# power.net
KiCad netlist of a schematic drawn in Altium Designer
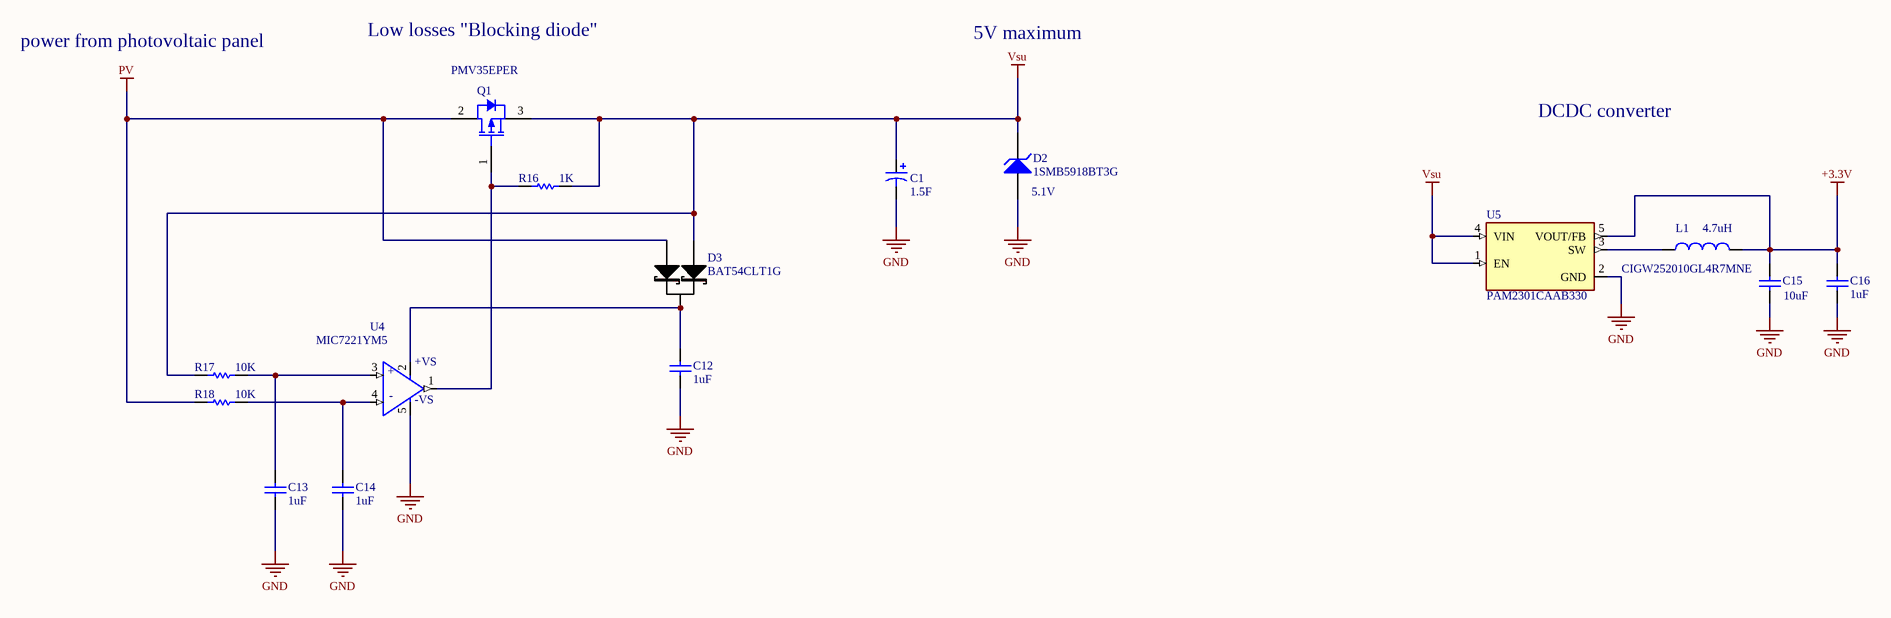
[diagram p0: power.SchDoc]

(export (version "E")
  (design (tool "Eeschema 10.0.6"))
  (components
    (comp (ref "C1")
      (value "1.5F")
      (footprint "SCMR22H155PSBB0")
      (description "Polarized Capacitor (Radial)")
      (fields (field (name "Comment") "Cap Pol1") (field (name "PUBLISHER") "Altium Limited"))
      (libsource (lib "Miscellaneous Devices") (part "Cap Pol1"))
    )
    (comp (ref "C12")
      (value "1uF")
      (footprint "6-0805_M")
      (description "Capacitor")
      (fields (field (name "PUBLISHER") "Altium Limited"))
      (libsource (lib "Miscellaneous Devices") (part "Cap"))
    )
    (comp (ref "C13")
      (value "1uF")
      (footprint "6-0805_M")
      (description "Capacitor")
      (fields (field (name "PUBLISHER") "Altium Limited"))
      (libsource (lib "Miscellaneous Devices") (part "Cap"))
    )
    (comp (ref "C14")
      (value "1uF")
      (footprint "6-0805_M")
      (description "Capacitor")
      (fields (field (name "PUBLISHER") "Altium Limited"))
      (libsource (lib "Miscellaneous Devices") (part "Cap"))
    )
    (comp (ref "C15")
      (value "10uF")
      (footprint "6-0805_M")
      (fields (field (name "PUBLISHER") "Altium Limited"))
      (libsource (lib "Miscellaneous Devices") (part "Cap"))
    )
    (comp (ref "C16")
      (value "1uF")
      (footprint "6-0805_M")
      (description "Capacitor")
      (fields (field (name "PUBLISHER") "Altium Limited"))
      (libsource (lib "Miscellaneous Devices") (part "Cap"))
    )
    (comp (ref "D2")
      (value "1SMB5918BT3G")
      (footprint "SMB")
      (description "Zener Diode")
      (fields (field (name "ALTIUM_VALUE") "5.1V") (field (name "PUBLISHER") "Altium Limited"))
      (libsource (lib "Miscellaneous Devices") (part "D Zener"))
    )
    (comp (ref "D3")
      (value "BAT54CLT1G")
      (footprint "SOT23-DUODIODE")
      (description "DUAL SCHOTTKY DIODE COMMON CATHODE")
      (fields
        (field (name "MANUFACTURER") "NXP Semiconductors")
        (field (name "MANUFACTURER PART NUMBER") "BAT54C,215")
      )
      (libsource (lib "vh_altium_library") (part "BAT54C-SOT23"))
    )
    (comp (ref "L1")
      (value "CIGW252010GL4R7MNE")
      (footprint "INDUCTOR_2520 - duplicate1")
      (description "Inductor")
      (fields (field (name "ALTIUM_VALUE") "4.7uH") (field (name "PUBLISHER") "Altium Limited"))
      (libsource (lib "Miscellaneous Devices") (part "Inductor"))
    )
    (comp (ref "Q1")
      (value "PMV35EPER")
      (footprint "PMV35EPER")
      (description "P-Channel MOSFET")
      (fields (field (name "PUBLISHER") "Altium Limited"))
      (libsource (lib "laf") (part "MOSFET-P"))
    )
    (comp (ref "R16")
      (value "1K")
      (footprint "6-0805_N")
      (description "Resistor")
      (fields (field (name "PUBLISHER") "Altium Limited"))
      (libsource (lib "Miscellaneous Devices") (part "Res1"))
    )
    (comp (ref "R17")
      (value "10K")
      (footprint "6-0805_N")
      (description "Resistor")
      (fields (field (name "PUBLISHER") "Altium Limited"))
      (libsource (lib "Miscellaneous Devices") (part "Res1"))
    )
    (comp (ref "R18")
      (value "10K")
      (footprint "6-0805_N")
      (description "Resistor")
      (fields (field (name "PUBLISHER") "Altium Limited"))
      (libsource (lib "Miscellaneous Devices") (part "Res1"))
    )
    (comp (ref "U4")
      (value "MIC7221YM5")
      (footprint "MIC7221YM5")
      (description "Comparator General Purpose Open Drain SOT-23-5")
      (fields (field (name "MP") "MIC7221YM5-TR") (field (name "MF") "Microchip"))
      (libsource (lib "laf") (part "MIC7221YM5-TR"))
    )
    (comp (ref "U5")
      (value "PAM2301CAAB330")
      (footprint "SOT95P280X100-5N")
      (description "Buck Switching Regulator IC Positive Fixed 1.2V 1 Output 800mA SOT-23-5 Thin, TSOT-23-5")
      (fields (field (name "MF") "Diodes Inc.") (field (name "MP") "PAM2301CAAB120"))
      (libsource (lib "laf") (part "PAM2301CAAB120"))
    )
  )
  (nets
    (net (code "1") (name "+3.3V") (class "Default")
      (node (ref "C15") (pin "2") (pinfunction "2_2") (pintype "passive"))
      (node (ref "C16") (pin "2") (pinfunction "2_2") (pintype "passive"))
      (node (ref "L1") (pin "2") (pinfunction "2_2") (pintype "passive"))
      (node (ref "U5") (pin "5") (pinfunction "VOUT/FB_5") (pintype "output"))
    )
    (net (code "2") (name "GND") (class "Default")
      (node (ref "C1") (pin "2") (pinfunction "2_2") (pintype "passive"))
      (node (ref "C12") (pin "1") (pinfunction "1_1") (pintype "passive"))
      (node (ref "C13") (pin "1") (pinfunction "1_1") (pintype "passive"))
      (node (ref "C14") (pin "1") (pinfunction "1_1") (pintype "passive"))
      (node (ref "C15") (pin "1") (pinfunction "1_1") (pintype "passive"))
      (node (ref "C16") (pin "1") (pinfunction "1_1") (pintype "passive"))
      (node (ref "D2") (pin "1") (pinfunction "A_1") (pintype "passive"))
      (node (ref "U4") (pin "5") (pinfunction "-VS_5") (pintype "power_in"))
      (node (ref "U5") (pin "2") (pinfunction "GND_2") (pintype "power_in"))
    )
    (net (code "3") (name "Net-(Q1-G)") (class "Default")
      (node (ref "Q1") (pin "1") (pinfunction "G_1") (pintype "passive"))
      (node (ref "R16") (pin "1") (pinfunction "1_1") (pintype "passive"))
      (node (ref "U4") (pin "1") (pinfunction "OUT_1") (pintype "output"))
    )
    (net (code "4") (name "Net-(U4-+VS)") (class "Default")
      (node (ref "C12") (pin "2") (pinfunction "2_2") (pintype "passive"))
      (node (ref "D3") (pin "3") (pinfunction "3_3") (pintype "passive"))
      (node (ref "U4") (pin "2") (pinfunction "+VS_2") (pintype "power_in"))
    )
    (net (code "5") (name "Net-(U4-IN+)") (class "Default")
      (node (ref "C13") (pin "2") (pinfunction "2_2") (pintype "passive"))
      (node (ref "R17") (pin "2") (pinfunction "2_2") (pintype "passive"))
      (node (ref "U4") (pin "3") (pinfunction "IN+_3") (pintype "input"))
    )
    (net (code "6") (name "Net-(U4-IN-)") (class "Default")
      (node (ref "C14") (pin "2") (pinfunction "2_2") (pintype "passive"))
      (node (ref "R18") (pin "2") (pinfunction "2_2") (pintype "passive"))
      (node (ref "U4") (pin "4") (pinfunction "IN-_4") (pintype "input"))
    )
    (net (code "7") (name "Net-(U5-SW)") (class "Default")
      (node (ref "L1") (pin "1") (pinfunction "1_1") (pintype "passive"))
      (node (ref "U5") (pin "3") (pinfunction "SW_3") (pintype "output"))
    )
    (net (code "8") (name "PV") (class "Default")
      (node (ref "D3") (pin "2") (pinfunction "2_2") (pintype "passive"))
      (node (ref "Q1") (pin "2") (pinfunction "D_2") (pintype "passive"))
      (node (ref "R18") (pin "1") (pinfunction "1_1") (pintype "passive"))
    )
    (net (code "9") (name "Vsu") (class "Default")
      (node (ref "C1") (pin "1") (pinfunction "1_1") (pintype "passive"))
      (node (ref "D2") (pin "2") (pinfunction "K_2") (pintype "passive"))
      (node (ref "D3") (pin "1") (pinfunction "1_1") (pintype "passive"))
      (node (ref "Q1") (pin "3") (pinfunction "S_3") (pintype "passive"))
      (node (ref "R16") (pin "2") (pinfunction "2_2") (pintype "passive"))
      (node (ref "R17") (pin "1") (pinfunction "1_1") (pintype "passive"))
      (node (ref "U5") (pin "1") (pinfunction "EN_1") (pintype "input"))
      (node (ref "U5") (pin "4") (pinfunction "VIN_4") (pintype "input"))
    )
  )
)
